# mains_motion.net
KiCad netlist of a schematic drawn in EAGLE
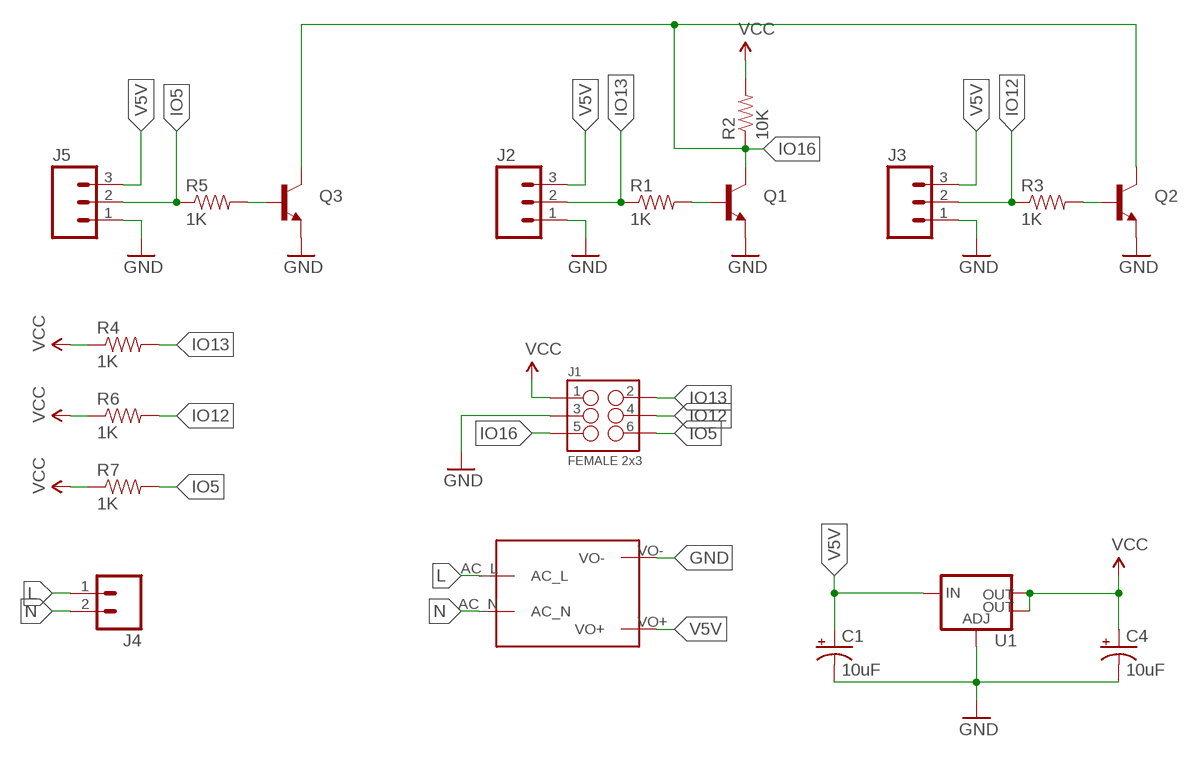
[diagram p0: schematic, sheet 1]

(export (version "E")
  (design (tool "Eeschema 10.0.6"))
  (components
    (comp (ref "C1")
      (value "10uF")
      (footprint "eagle-import:EIA3216-KIT")
      (libsource (lib "eagle-import") (part "CAP_POL1206-KIT"))
    )
    (comp (ref "C4")
      (value "10uF")
      (footprint "eagle-import:EIA3216-KIT")
      (libsource (lib "eagle-import") (part "CAP_POL1206-KIT"))
    )
    (comp (ref "J1")
      (value "FEMALE 2x3")
      (footprint "eagle-import:2X3-SHROUDED")
      (libsource (lib "eagle-import") (part "M03X2SHROUD"))
    )
    (comp (ref "J2")
      (value "M03PTH")
      (footprint "eagle-import:1X03")
      (libsource (lib "eagle-import") (part "M03PTH"))
    )
    (comp (ref "J3")
      (value "M03PTH")
      (footprint "eagle-import:1X03")
      (libsource (lib "eagle-import") (part "M03PTH"))
    )
    (comp (ref "J4")
      (value "M023.5MM")
      (footprint "eagle-import:SCREWTERMINAL-3.5MM-2")
      (libsource (lib "eagle-import") (part "M023.5MM"))
    )
    (comp (ref "J5")
      (value "M03PTH")
      (footprint "eagle-import:1X03")
      (libsource (lib "eagle-import") (part "M03PTH"))
    )
    (comp (ref "Q1")
      (value "TRANSISTOR_NPNSOT23-3")
      (footprint "eagle-import:SOT23-3")
      (libsource (lib "eagle-import") (part "TRANSISTOR_NPNSOT23-3"))
    )
    (comp (ref "Q2")
      (value "TRANSISTOR_NPNSOT23-3")
      (footprint "eagle-import:SOT23-3")
      (libsource (lib "eagle-import") (part "TRANSISTOR_NPNSOT23-3"))
    )
    (comp (ref "Q3")
      (value "TRANSISTOR_NPNSOT23-3")
      (footprint "eagle-import:SOT23-3")
      (libsource (lib "eagle-import") (part "TRANSISTOR_NPNSOT23-3"))
    )
    (comp (ref "R1")
      (value "1K")
      (footprint "eagle-import:0805")
      (libsource (lib "eagle-import") (part "RESISTOR0805-RES"))
    )
    (comp (ref "R2")
      (value "10K")
      (footprint "eagle-import:0805")
      (libsource (lib "eagle-import") (part "RESISTOR0805-RES"))
    )
    (comp (ref "R3")
      (value "1K")
      (footprint "eagle-import:0805")
      (libsource (lib "eagle-import") (part "RESISTOR0805-RES"))
    )
    (comp (ref "R4")
      (value "1K")
      (footprint "eagle-import:0805")
      (libsource (lib "eagle-import") (part "RESISTOR0805-RES"))
    )
    (comp (ref "R5")
      (value "1K")
      (footprint "eagle-import:0805")
      (libsource (lib "eagle-import") (part "RESISTOR0805-RES"))
    )
    (comp (ref "R6")
      (value "1K")
      (footprint "eagle-import:0805")
      (libsource (lib "eagle-import") (part "RESISTOR0805-RES"))
    )
    (comp (ref "R7")
      (value "1K")
      (footprint "eagle-import:0805")
      (libsource (lib "eagle-import") (part "RESISTOR0805-RES"))
    )
    (comp (ref "U$1")
      (value "MAINS_CONVERTERS")
      (footprint "eagle-import:HLK-PM01")
      (libsource (lib "eagle-import") (part "MAINS_CONVERTERS"))
    )
    (comp (ref "U1")
      (value "V_REG_LM1117SOT223")
      (footprint "eagle-import:SOT223")
      (libsource (lib "eagle-import") (part "V_REG_LM1117SOT223"))
    )
  )
  (nets
    (net (code "1") (name "GND") (class "Default")
      (node (ref "C1") (pin "C") (pinfunction "-_C") (pintype "passive"))
      (node (ref "C4") (pin "C") (pinfunction "-_C") (pintype "passive"))
      (node (ref "J1") (pin "3") (pinfunction "3_3") (pintype "bidirectional"))
      (node (ref "J2") (pin "1") (pinfunction "1_1") (pintype "passive"))
      (node (ref "J3") (pin "1") (pinfunction "1_1") (pintype "passive"))
      (node (ref "J5") (pin "1") (pinfunction "1_1") (pintype "passive"))
      (node (ref "Q1") (pin "2") (pinfunction "E_2") (pintype "passive"))
      (node (ref "Q2") (pin "2") (pinfunction "E_2") (pintype "passive"))
      (node (ref "Q3") (pin "2") (pinfunction "E_2") (pintype "passive"))
      (node (ref "U$1") (pin "VO-") (pinfunction "VO-_VO-") (pintype "output"))
      (node (ref "U1") (pin "1") (pinfunction "ADJ_1") (pintype "input"))
    )
    (net (code "2") (name "IO5") (class "Default")
      (node (ref "J1") (pin "6") (pinfunction "6_6") (pintype "bidirectional"))
      (node (ref "J5") (pin "2") (pinfunction "2_2") (pintype "passive"))
      (node (ref "R5") (pin "1") (pinfunction "1_1") (pintype "passive"))
      (node (ref "R7") (pin "2") (pinfunction "2_2") (pintype "passive"))
    )
    (net (code "3") (name "IO12") (class "Default")
      (node (ref "J1") (pin "4") (pinfunction "4_4") (pintype "bidirectional"))
      (node (ref "J3") (pin "2") (pinfunction "2_2") (pintype "passive"))
      (node (ref "R3") (pin "1") (pinfunction "1_1") (pintype "passive"))
      (node (ref "R6") (pin "2") (pinfunction "2_2") (pintype "passive"))
    )
    (net (code "4") (name "IO13") (class "Default")
      (node (ref "J1") (pin "2") (pinfunction "2_2") (pintype "bidirectional"))
      (node (ref "J2") (pin "2") (pinfunction "2_2") (pintype "passive"))
      (node (ref "R1") (pin "1") (pinfunction "1_1") (pintype "passive"))
      (node (ref "R4") (pin "2") (pinfunction "2_2") (pintype "passive"))
    )
    (net (code "5") (name "IO16") (class "Default")
      (node (ref "J1") (pin "5") (pinfunction "5_5") (pintype "bidirectional"))
      (node (ref "Q1") (pin "3") (pinfunction "C_3") (pintype "passive"))
      (node (ref "Q2") (pin "3") (pinfunction "C_3") (pintype "passive"))
      (node (ref "Q3") (pin "3") (pinfunction "C_3") (pintype "passive"))
      (node (ref "R2") (pin "1") (pinfunction "1_1") (pintype "passive"))
    )
    (net (code "6") (name "L") (class "Default")
      (node (ref "J4") (pin "1") (pinfunction "1_1") (pintype "passive"))
      (node (ref "U$1") (pin "AC_L") (pinfunction "AC_L_AC_L") (pintype "input"))
    )
    (net (code "7") (name "N") (class "Default")
      (node (ref "J4") (pin "2") (pinfunction "2_2") (pintype "passive"))
      (node (ref "U$1") (pin "AC_N") (pinfunction "AC_N_AC_N") (pintype "input"))
    )
    (net (code "8") (name "Net-(Q1-B)") (class "Default")
      (node (ref "Q1") (pin "1") (pinfunction "B_1") (pintype "passive"))
      (node (ref "R1") (pin "2") (pinfunction "2_2") (pintype "passive"))
    )
    (net (code "9") (name "Net-(Q2-B)") (class "Default")
      (node (ref "Q2") (pin "1") (pinfunction "B_1") (pintype "passive"))
      (node (ref "R3") (pin "2") (pinfunction "2_2") (pintype "passive"))
    )
    (net (code "10") (name "Net-(Q3-B)") (class "Default")
      (node (ref "Q3") (pin "1") (pinfunction "B_1") (pintype "passive"))
      (node (ref "R5") (pin "2") (pinfunction "2_2") (pintype "passive"))
    )
    (net (code "11") (name "V5V") (class "Default")
      (node (ref "C1") (pin "A") (pinfunction "+_A") (pintype "passive"))
      (node (ref "J2") (pin "3") (pinfunction "3_3") (pintype "passive"))
      (node (ref "J3") (pin "3") (pinfunction "3_3") (pintype "passive"))
      (node (ref "J5") (pin "3") (pinfunction "3_3") (pintype "passive"))
      (node (ref "U$1") (pin "VO+") (pinfunction "VO+_VO+") (pintype "output"))
      (node (ref "U1") (pin "3") (pinfunction "IN_3") (pintype "input"))
    )
    (net (code "12") (name "VCC") (class "Default")
      (node (ref "C4") (pin "A") (pinfunction "+_A") (pintype "passive"))
      (node (ref "J1") (pin "1") (pinfunction "1_1") (pintype "bidirectional"))
      (node (ref "R2") (pin "2") (pinfunction "2_2") (pintype "passive"))
      (node (ref "R4") (pin "1") (pinfunction "1_1") (pintype "passive"))
      (node (ref "R6") (pin "1") (pinfunction "1_1") (pintype "passive"))
      (node (ref "R7") (pin "1") (pinfunction "1_1") (pintype "passive"))
      (node (ref "U1") (pin "2") (pinfunction "OUT_2") (pintype "output"))
      (node (ref "U1") (pin "4") (pinfunction "OUT_4") (pintype "output"))
    )
  )
)
